# Sheet1.net
KiCad netlist of a schematic drawn in Altium Designer
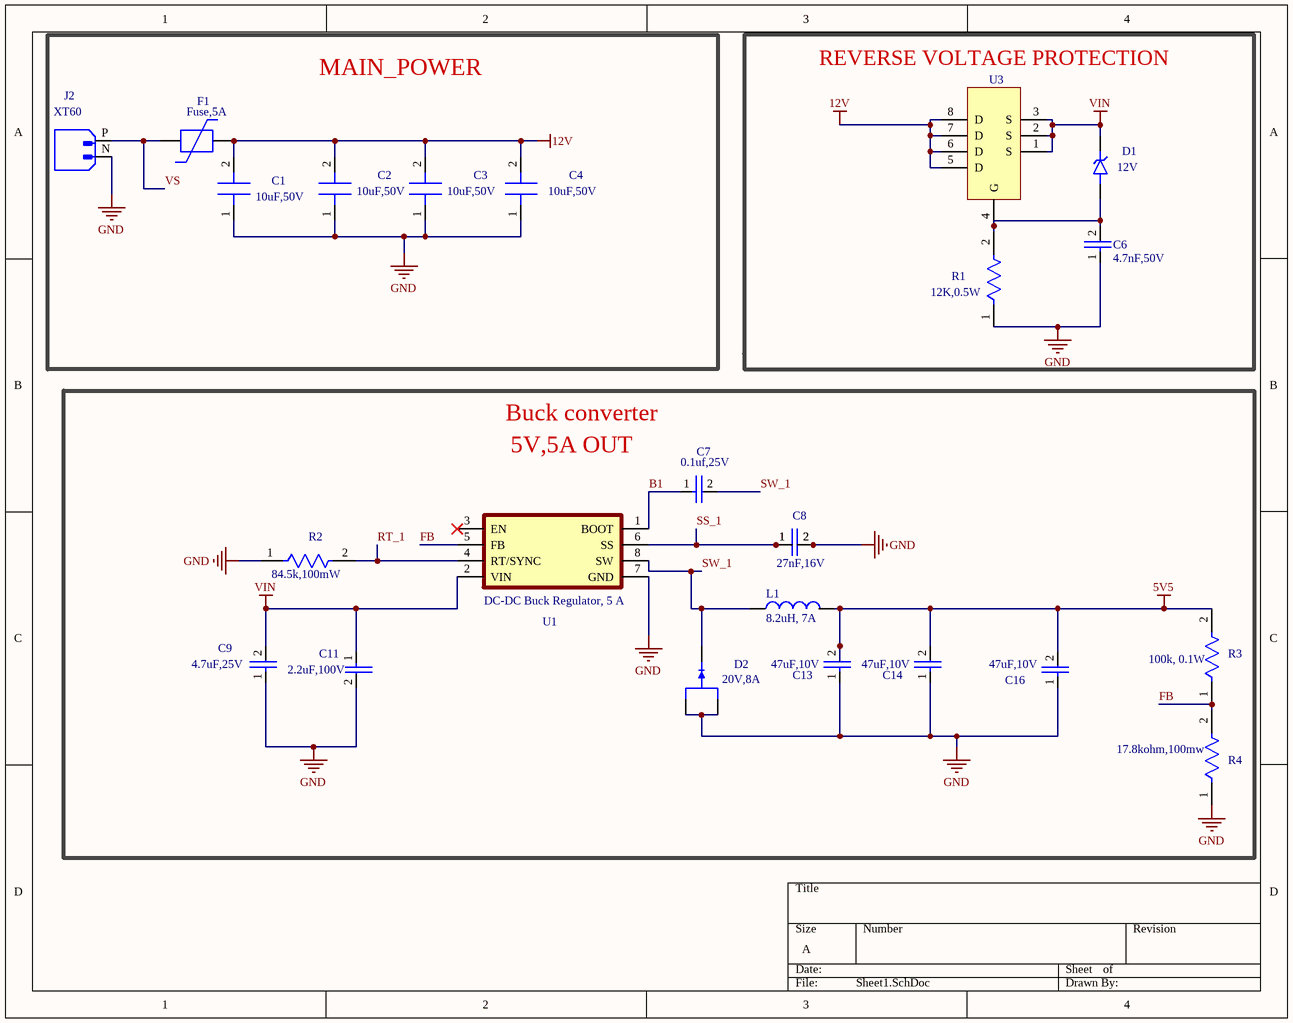
[diagram p0: Sheet1.SchDoc]

(export (version "E")
  (design (tool "Eeschema 10.0.6"))
  (components
    (comp (ref "C1")
      (value "10uF,50V")
      (footprint "CL31A106KBHNNNE")
      (description "CAP CER 10uF 50V X5R 1206")
      (libsource (lib "Schlib1") (part "CL31A106KBHNNNE"))
    )
    (comp (ref "C2")
      (value "10uF,50V")
      (footprint "CL31A106KBHNNNE")
      (description "CAP CER 10uF 50V X5R 1206")
      (libsource (lib "Schlib1") (part "CL31A106KBHNNNE"))
    )
    (comp (ref "C3")
      (value "10uF,50V")
      (footprint "CL31A106KBHNNNE")
      (description "CAP CER 10uF 50V X5R 1206")
      (libsource (lib "Schlib1") (part "CL31A106KBHNNNE"))
    )
    (comp (ref "C4")
      (value "10uF,50V")
      (footprint "CL31A106KBHNNNE")
      (description "CAP CER 10uF 50V X5R 1206")
      (libsource (lib "Schlib1") (part "CL31A106KBHNNNE"))
    )
    (comp (ref "C6")
      (value "4.7nF,50V")
      (footprint "C0603C472F5GACTU")
      (description "50V 4.7nF C0G 0603 Ceramic Capacitors ROHS")
      (fields (field (name "MANAFUCTURER PART NUMBER") "C0603C472F5GACTU"))
      (libsource (lib "Schlib1") (part "C0603C472F5GACTU"))
    )
    (comp (ref "C7")
      (value "0.1uf,25V")
      (footprint "CC0603KRX7R8BB104")
      (description "25V 100nF X7R ±10% 0603 Ceramic Capacitors ROHS")
      (fields (field (name "MANAFUCTURER PART NUMBER") "CC0603KRX7R8BB104"))
      (libsource (lib "Schlib1") (part "CC0603KRX7R8BB104"))
    )
    (comp (ref "C8")
      (value "27nF,16V")
      (footprint "C0805C273K4HACAUTO")
      (description "16V 27nF X8R ±10% 0805 Ceramic Capacitors ROHS")
      (libsource (lib "Schlib1") (part "C0805C273K4HACAUTO"))
    )
    (comp (ref "C9")
      (value "4.7uF,25V")
      (footprint "GRM188R61E475KE11D")
      (description "25V 4.7uF X5R ±10% 0603 Ceramic Capacitors ROHS")
      (fields (field (name "MANAFUCTURER PART NUMBER") "GRM188R61E475KE11D"))
      (libsource (lib "Schlib1") (part "GRM188R61E475KE11D"))
    )
    (comp (ref "C11")
      (value "2.2uF,100V")
      (footprint "CL31A106KBHNNNE")
      (description "100V 2.2uF X7R ±10% 1206 Ceramic Capacitors ROHS")
      (fields (field (name "MANAFUCTURER PART NUMBER") "CL31B225KCHSNNE"))
      (libsource (lib "Schlib1") (part "CL31B225KCHSNNE"))
    )
    (comp (ref "C13")
      (value "47uF,10V")
      (footprint "GRM31CR61A476ME15L")
      (description "10V 47uF X5R ±20% 1206 Ceramic Capacitors ROHS")
      (fields (field (name "MANAFUCTURER PART NUMBER") "GRM31CR61A476ME15L"))
      (libsource (lib "Schlib1") (part "GRM31CR61A476ME15L"))
    )
    (comp (ref "C14")
      (value "47uF,10V")
      (footprint "GRM31CR61A476ME15L")
      (description "10V 47uF X5R ±20% 1206 Ceramic Capacitors ROHS")
      (fields (field (name "MANAFUCTURER PART NUMBER") "GRM31CR61A476ME15L"))
      (libsource (lib "Schlib1") (part "GRM31CR61A476ME15L"))
    )
    (comp (ref "C16")
      (value "47uF,10V")
      (footprint "GRM31CR61A476ME15L")
      (description "10V 47uF X5R ±20% 1206 Ceramic Capacitors ROHS")
      (fields (field (name "MANAFUCTURER PART NUMBER") "GRM31CR61A476ME15L"))
      (libsource (lib "Schlib1") (part "GRM31CR61A476ME15L"))
    )
    (comp (ref "D1")
      (value "12V")
      (footprint "SMAZ12-13-F")
      (description "DIODE ZENER 12V 1W SMA")
      (fields (field (name "MANAFUCTURER PART NUMBER") "SMAZ12-13-F"))
      (libsource (lib "Schlib1") (part "SMAZ12-13-F"))
    )
    (comp (ref "D2")
      (value "20V,8A")
      (footprint "SS12P2L-M3/86A")
      (description "20V 560mV@12A 12A TO-277A Single Diodes ROHS")
      (fields (field (name "MANAFUCTURER PART NUMBER") "SS12P2L-M3/86A"))
      (libsource (lib "Schlib1") (part "SS12P2L-M3/86A"))
    )
    (comp (ref "F1")
      (value "Fuse,5A")
      (footprint "2920L500/16MR")
      (description "16V 5A 40A 10A 5mΩ 2920 PTC Resettable Fuses ROHS")
      (libsource (lib "Schlib1") (part "2920L500/16MR"))
    )
    (comp (ref "J2")
      (value "XT60")
      (footprint "XT60-M")
      (description "Plug; DC supply; XT60; male; PIN: 2; for cable; soldered; 30A; 500V")
      (libsource (lib "Schlib1") (part "XT60-M"))
    )
    (comp (ref "L1")
      (value "8.2uH, 7A")
      (footprint "SCIHP1040-8R2M")
      (description "7A 8.2uH ±20% 10A 31mΩ SMD,11.5x10.2mm Fixed Inductors ROHS")
      (fields (field (name "MANAFUCTURER PART NUMBER") "SCIHP1040-8R2M"))
      (libsource (lib "Schlib1") (part "SCIHP1040-8R2M"))
    )
    (comp (ref "R1")
      (value "12K,0.5W")
      (footprint "CRGP1206F12K")
      (fields (field (name "MANUFUCTURER PART NUMBER") "CRGP1206F12K"))
      (libsource (lib "Schlib1") (part "CRGP1206F12K"))
    )
    (comp (ref "R2")
      (value "84.5k,100mW")
      (footprint "RC0603FR-0784K5L")
      (description "100mW 84.5kΩ 75V ±100ppm/℃ Thick Film Resistor ±1% 0603 Chip Resistor - Surface Mount ROHS")
      (fields (field (name "MANAFUCTURER PART NUMBER") "RC0603FR-0784K5L"))
      (libsource (lib "Schlib1") (part "RC0603FR-0784K5L"))
    )
    (comp (ref "R3")
      (value "100k, 0.1W")
      (footprint "RT0603CRC07100KL")
      (description "100 kOhms ±0.25% 0.1W, 1/10W Chip Resistor 0603 (1608 Metric) - Thin Film")
      (fields (field (name "MANAFUCTURER PART NUMBER") "RT0603CRE07100KL"))
      (libsource (lib "Schlib1") (part "100 kOhms ±0.25% 0.1W, 1/10W Chip Resistor 0603 (1608 Metric) - Thin Film"))
    )
    (comp (ref "R4")
      (value "17.8kohm,100mw")
      (footprint "RC0603FR-0717K8L")
      (description "100mW 17.8kΩ 75V ±100ppm/℃ Thick Film Resistor ±1% 0603 Chip Resistor - Surface Mount ROHS")
      (fields (field (name "MANAFUCTURER PART NUMBER") "RC0603FR-0717K8L"))
      (libsource (lib "Schlib1") (part "RC0603FR-0717K8L"))
    )
    (comp (ref "U1")
      (value "DC-DC Buck Regulator, 5 A")
      (footprint "LMR14050SDDAR")
      (fields (field (name "MANAFUCTURER PART NUMBER") "LMR14050SDDAR"))
      (libsource (lib "Schlib1") (part "LMR14050SDDAR"))
    )
    (comp (ref "U3")
      (value "P channel mosfet")
      (footprint "SI4435FDY-T1-GE3")
      (description "30V 12.6A 19mΩ@10V,9A 2.2W 2.2V 1 P-Channel SO-8 Single FETs, MOSFETs ROHS")
      (libsource (lib "Schlib1") (part "SI4435FDY-T1-GE3"))
    )
  )
  (nets
    (net (code "1") (name "/B1") (class "Default")
      (node (ref "C7") (pin "1") (pinfunction "1_1") (pintype "passive"))
      (node (ref "U1") (pin "1") (pinfunction "BOOT_1") (pintype "passive"))
    )
    (net (code "2") (name "/FB") (class "Default")
      (node (ref "R3") (pin "1") (pinfunction "1_1") (pintype "passive"))
      (node (ref "R4") (pin "2") (pinfunction "2_2") (pintype "passive"))
      (node (ref "U1") (pin "5") (pinfunction "FB_5") (pintype "passive"))
    )
    (net (code "3") (name "/RT_1") (class "Default")
      (node (ref "R2") (pin "2") (pinfunction "2_2") (pintype "passive"))
      (node (ref "U1") (pin "4") (pinfunction "RT/SYNC_4") (pintype "passive"))
    )
    (net (code "4") (name "/SS_1") (class "Default")
      (node (ref "C8") (pin "1") (pinfunction "1_1") (pintype "passive"))
      (node (ref "U1") (pin "6") (pinfunction "SS_6") (pintype "passive"))
    )
    (net (code "5") (name "/SW_1") (class "Default")
      (node (ref "C7") (pin "2") (pinfunction "2_2") (pintype "passive"))
      (node (ref "D2") (pin "3") (pinfunction "K_3") (pintype "passive"))
      (node (ref "L1") (pin "1") (pinfunction "1_1") (pintype "passive"))
      (node (ref "U1") (pin "8") (pinfunction "SW_8") (pintype "passive"))
    )
    (net (code "6") (name "/VS") (class "Default")
      (node (ref "F1") (pin "1") (pinfunction "1_1") (pintype "passive"))
      (node (ref "J2") (pin "P") (pinfunction "XT60_P") (pintype "passive"))
    )
    (net (code "7") (name "5V5") (class "Default")
      (node (ref "C13") (pin "2") (pinfunction "2_2") (pintype "passive"))
      (node (ref "C14") (pin "2") (pinfunction "2_2") (pintype "passive"))
      (node (ref "C16") (pin "2") (pinfunction "2_2") (pintype "passive"))
      (node (ref "L1") (pin "2") (pinfunction "2_2") (pintype "passive"))
      (node (ref "R3") (pin "2") (pinfunction "2_2") (pintype "passive"))
    )
    (net (code "8") (name "12V") (class "Default")
      (node (ref "C1") (pin "2") (pinfunction "2_2") (pintype "passive"))
      (node (ref "C2") (pin "2") (pinfunction "2_2") (pintype "passive"))
      (node (ref "C3") (pin "2") (pinfunction "2_2") (pintype "passive"))
      (node (ref "C4") (pin "2") (pinfunction "2_2") (pintype "passive"))
      (node (ref "F1") (pin "2") (pinfunction "2_2") (pintype "passive"))
      (node (ref "U3") (pin "5") (pinfunction "D_5") (pintype "passive"))
      (node (ref "U3") (pin "6") (pinfunction "D_6") (pintype "passive"))
      (node (ref "U3") (pin "7") (pinfunction "D_7") (pintype "passive"))
      (node (ref "U3") (pin "8") (pinfunction "D_8") (pintype "passive"))
    )
    (net (code "9") (name "GND") (class "Default")
      (node (ref "C1") (pin "1") (pinfunction "1_1") (pintype "passive"))
      (node (ref "C11") (pin "2") (pinfunction "2_2") (pintype "passive"))
      (node (ref "C13") (pin "1") (pinfunction "1_1") (pintype "passive"))
      (node (ref "C14") (pin "1") (pinfunction "1_1") (pintype "passive"))
      (node (ref "C16") (pin "1") (pinfunction "1_1") (pintype "passive"))
      (node (ref "C2") (pin "1") (pinfunction "1_1") (pintype "passive"))
      (node (ref "C3") (pin "1") (pinfunction "1_1") (pintype "passive"))
      (node (ref "C4") (pin "1") (pinfunction "1_1") (pintype "passive"))
      (node (ref "C6") (pin "1") (pinfunction "1_1") (pintype "passive"))
      (node (ref "C8") (pin "2") (pinfunction "2_2") (pintype "passive"))
      (node (ref "C9") (pin "1") (pinfunction "1_1") (pintype "passive"))
      (node (ref "D2") (pin "1") (pinfunction "A1_1") (pintype "passive"))
      (node (ref "D2") (pin "2") (pinfunction "A2_2") (pintype "passive"))
      (node (ref "J2") (pin "N") (pinfunction "XT60_N") (pintype "passive"))
      (node (ref "R1") (pin "1") (pinfunction "1_1") (pintype "passive"))
      (node (ref "R2") (pin "1") (pinfunction "1_1") (pintype "passive"))
      (node (ref "R4") (pin "1") (pinfunction "1_1") (pintype "passive"))
      (node (ref "U1") (pin "7") (pinfunction "GND_7") (pintype "passive"))
    )
    (net (code "10") (name "Net-(D1-A)") (class "Default")
      (node (ref "C6") (pin "2") (pinfunction "2_2") (pintype "passive"))
      (node (ref "D1") (pin "2") (pinfunction "A_2") (pintype "passive"))
      (node (ref "R1") (pin "2") (pinfunction "2_2") (pintype "passive"))
      (node (ref "U3") (pin "4") (pinfunction "G_4") (pintype "passive"))
    )
    (net (code "11") (name "VIN") (class "Default")
      (node (ref "C11") (pin "1") (pinfunction "1_1") (pintype "passive"))
      (node (ref "C9") (pin "2") (pinfunction "2_2") (pintype "passive"))
      (node (ref "D1") (pin "1") (pinfunction "K_1") (pintype "passive"))
      (node (ref "U1") (pin "2") (pinfunction "VIN_2") (pintype "passive"))
      (node (ref "U3") (pin "1") (pinfunction "S_1") (pintype "passive"))
      (node (ref "U3") (pin "2") (pinfunction "S_2") (pintype "passive"))
      (node (ref "U3") (pin "3") (pinfunction "S_3") (pintype "passive"))
    )
    (net (code "12") (name "unconnected-(U1-EN-Pad3)") (class "Default")
      (node (ref "U1") (pin "3") (pinfunction "EN_3") (pintype "passive+no_connect"))
    )
  )
)
